# MCU_STM32L011.net
KiCad netlist of a schematic drawn in Altium Designer
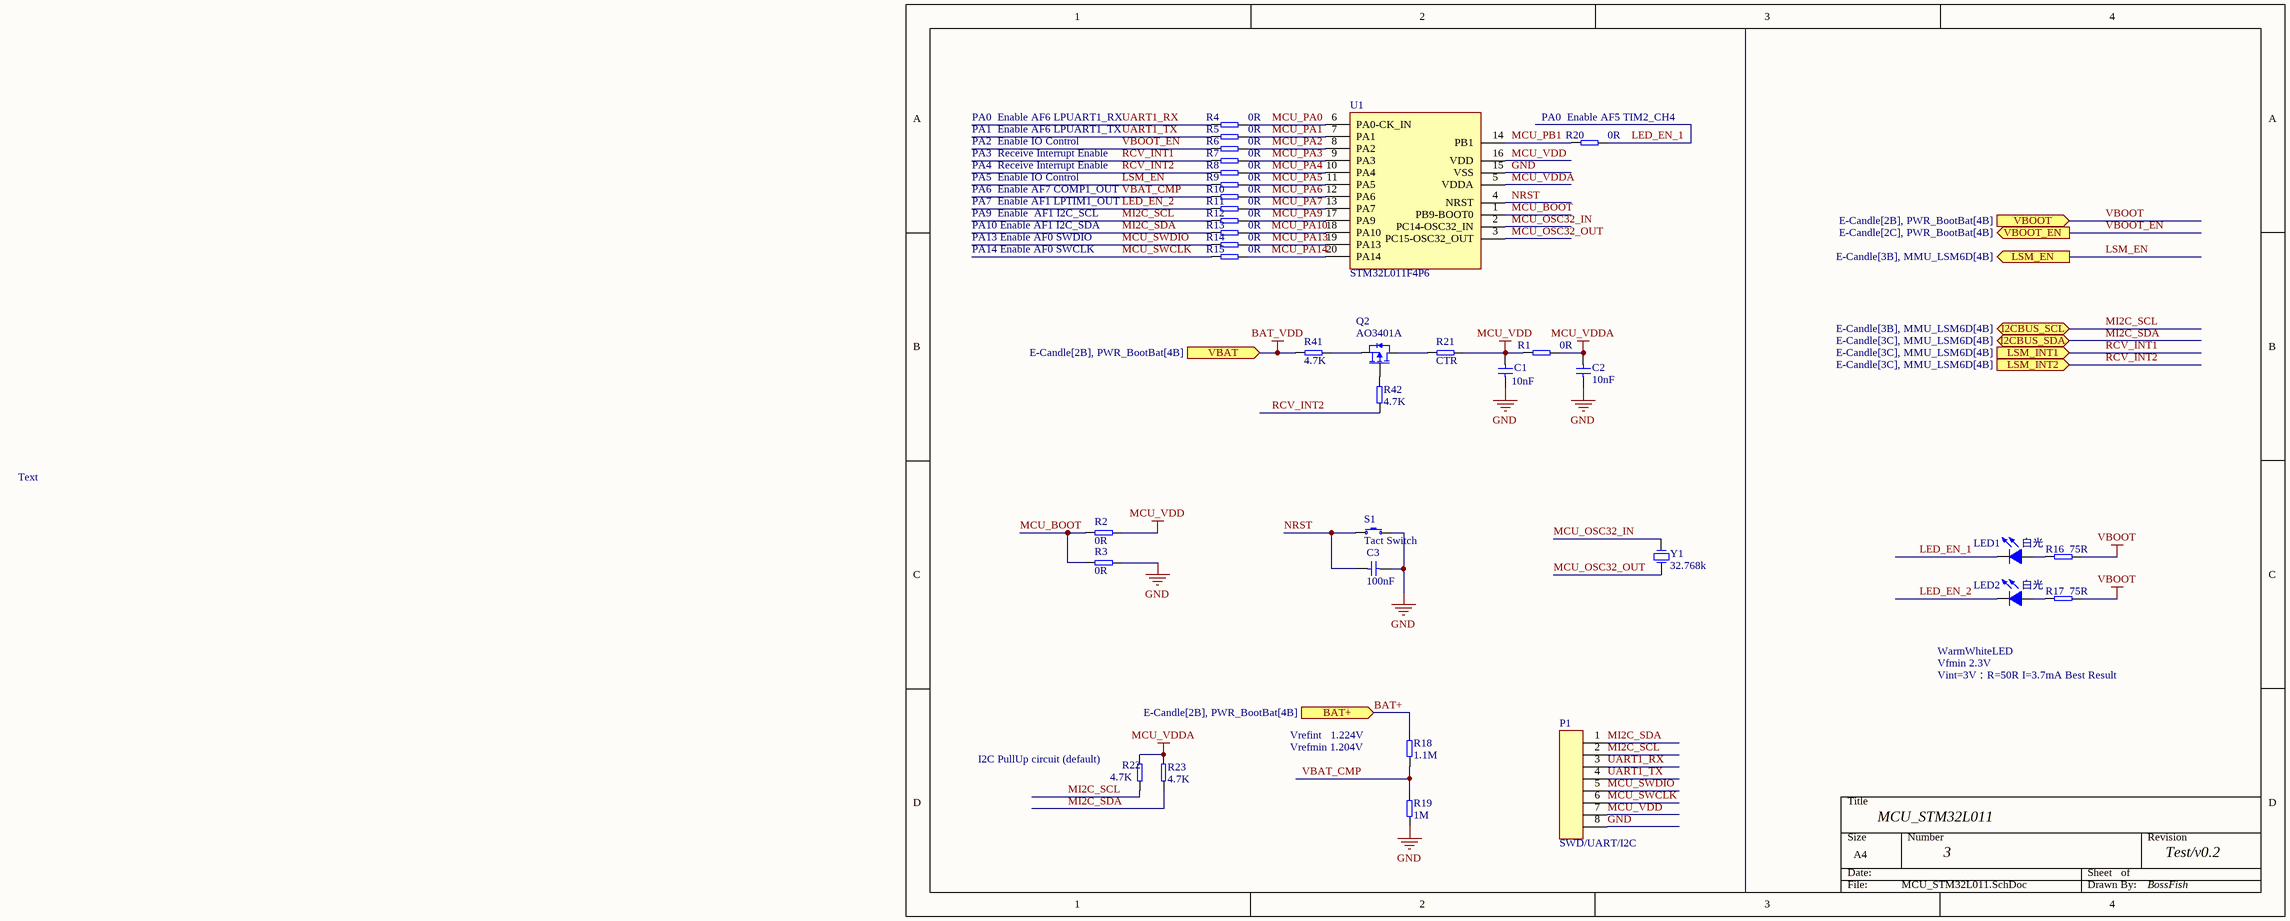
[diagram p0: MCU_STM32L011.SchDoc]

(export (version "E")
  (design (tool "Eeschema 10.0.6"))
  (components
    (comp (ref "C1") (value "10nF") (footprint "0603-C") (libsource (lib "Schlib1") (part "Cap")))
    (comp (ref "C2") (value "10nF") (footprint "0603-C") (libsource (lib "Schlib1") (part "Cap")))
    (comp (ref "C3") (value "100nF") (footprint "0603-C") (libsource (lib "Schlib1") (part "Cap")))
    (comp (ref "LED1") (value "白光") (footprint "0805-LED") (libsource (lib "Schlib1") (part "LED")))
    (comp (ref "LED2") (value "白光") (footprint "0805-LED") (libsource (lib "Schlib1") (part "LED")))
    (comp (ref "P1")
      (value "SWD/UART/I2C")
      (footprint "2.54mm 1x8P")
      (libsource (lib "Schlib1") (part "Header 1x8P"))
    )
    (comp (ref "Q2") (value "AO3401A") (footprint "SOT-23-3") (libsource (lib "Schlib1") (part "MOSFET-P")))
    (comp (ref "R1") (value "0R") (footprint "0603-R") (libsource (lib "Schlib1") (part "Res")))
    (comp (ref "R2") (value "0R") (footprint "0603-R") (libsource (lib "Schlib1") (part "Res")))
    (comp (ref "R3") (value "0R") (footprint "0603-R") (libsource (lib "Schlib1") (part "Res")))
    (comp (ref "R4") (value "0R") (footprint "0603-R") (libsource (lib "Schlib1") (part "Res")))
    (comp (ref "R5") (value "0R") (footprint "0603-R") (libsource (lib "Schlib1") (part "Res")))
    (comp (ref "R6") (value "0R") (footprint "0603-R") (libsource (lib "Schlib1") (part "Res")))
    (comp (ref "R7") (value "0R") (footprint "0603-R") (libsource (lib "Schlib1") (part "Res")))
    (comp (ref "R8") (value "0R") (footprint "0603-R") (libsource (lib "Schlib1") (part "Res")))
    (comp (ref "R9") (value "0R") (footprint "0603-R") (libsource (lib "Schlib1") (part "Res")))
    (comp (ref "R10") (value "0R") (footprint "0603-R") (libsource (lib "Schlib1") (part "Res")))
    (comp (ref "R11") (value "0R") (footprint "0603-R") (libsource (lib "Schlib1") (part "Res")))
    (comp (ref "R12") (value "0R") (footprint "0603-R") (libsource (lib "Schlib1") (part "Res")))
    (comp (ref "R13") (value "0R") (footprint "0603-R") (libsource (lib "Schlib1") (part "Res")))
    (comp (ref "R14") (value "0R") (footprint "0603-R") (libsource (lib "Schlib1") (part "Res")))
    (comp (ref "R15") (value "0R") (footprint "0603-R") (libsource (lib "Schlib1") (part "Res")))
    (comp (ref "R16") (value "75R") (footprint "0603-R") (libsource (lib "Schlib1") (part "Res")))
    (comp (ref "R17") (value "75R") (footprint "0603-R") (libsource (lib "Schlib1") (part "Res")))
    (comp (ref "R18") (value "1.1M") (footprint "0603-R") (libsource (lib "Schlib1") (part "Res")))
    (comp (ref "R19") (value "1M") (footprint "0603-R") (libsource (lib "Schlib1") (part "Res")))
    (comp (ref "R20") (value "0R") (footprint "0603-R") (libsource (lib "Schlib1") (part "Res")))
    (comp (ref "R21") (value "CTR") (footprint "0603-R") (libsource (lib "Schlib1") (part "Res")))
    (comp (ref "R22") (value "4.7K") (footprint "0603-R") (libsource (lib "Schlib1") (part "Res")))
    (comp (ref "R23") (value "4.7K") (footprint "0603-R") (libsource (lib "Schlib1") (part "Res")))
    (comp (ref "R41") (value "4.7K") (footprint "0603-R") (libsource (lib "Schlib1") (part "Res")))
    (comp (ref "R42") (value "4.7K") (footprint "0603-R") (libsource (lib "Schlib1") (part "Res")))
    (comp (ref "S1")
      (value "Tact Switch")
      (footprint "TS-3025")
      (libsource (lib "Schlib1") (part "Tact Switch"))
    )
    (comp (ref "U1")
      (value "STM32L011F4P6")
      (footprint "TSSOP-20")
      (libsource (lib "Schlib1") (part "STM32L011F4P6"))
    )
    (comp (ref "Y1") (value "32.768k") (footprint "SMD3215-2P") (libsource (lib "Schlib1") (part "XTAL")))
  )
  (nets
    (net (code "1") (name "/BAT+") (class "Default")
      (node (ref "R18") (pin "2") (pinfunction "2_2") (pintype "passive"))
    )
    (net (code "2") (name "/LED_EN_1") (class "Default")
      (node (ref "LED1") (pin "1") (pinfunction "1_1") (pintype "passive"))
      (node (ref "R20") (pin "1") (pinfunction "1_1") (pintype "passive"))
    )
    (net (code "3") (name "/LED_EN_2") (class "Default")
      (node (ref "LED2") (pin "1") (pinfunction "1_1") (pintype "passive"))
      (node (ref "R11") (pin "2") (pinfunction "2_2") (pintype "passive"))
    )
    (net (code "4") (name "/LSM_EN") (class "Default")
      (node (ref "R9") (pin "2") (pinfunction "2_2") (pintype "passive"))
    )
    (net (code "5") (name "/MCU_BOOT") (class "Default")
      (node (ref "R2") (pin "2") (pinfunction "2_2") (pintype "passive"))
      (node (ref "R3") (pin "2") (pinfunction "2_2") (pintype "passive"))
      (node (ref "U1") (pin "1") (pinfunction "PB9-BOOT0_1") (pintype "passive"))
    )
    (net (code "6") (name "/MCU_OSC32_IN") (class "Default")
      (node (ref "U1") (pin "2") (pinfunction "PC14-OSC32_IN_2") (pintype "passive"))
      (node (ref "Y1") (pin "2") (pinfunction "2_2") (pintype "passive"))
    )
    (net (code "7") (name "/MCU_OSC32_OUT") (class "Default")
      (node (ref "U1") (pin "3") (pinfunction "PC15-OSC32_OUT_3") (pintype "passive"))
      (node (ref "Y1") (pin "1") (pinfunction "1_1") (pintype "passive"))
    )
    (net (code "8") (name "/MCU_PA0") (class "Default")
      (node (ref "R4") (pin "1") (pinfunction "1_1") (pintype "passive"))
      (node (ref "U1") (pin "6") (pinfunction "PA0-CK_IN_6") (pintype "passive"))
    )
    (net (code "9") (name "/MCU_PA1") (class "Default")
      (node (ref "R5") (pin "1") (pinfunction "1_1") (pintype "passive"))
      (node (ref "U1") (pin "7") (pinfunction "PA1_7") (pintype "passive"))
    )
    (net (code "10") (name "/MCU_PA2") (class "Default")
      (node (ref "R6") (pin "1") (pinfunction "1_1") (pintype "passive"))
      (node (ref "U1") (pin "8") (pinfunction "PA2_8") (pintype "passive"))
    )
    (net (code "11") (name "/MCU_PA3") (class "Default")
      (node (ref "R7") (pin "1") (pinfunction "1_1") (pintype "passive"))
      (node (ref "U1") (pin "9") (pinfunction "PA3_9") (pintype "passive"))
    )
    (net (code "12") (name "/MCU_PA4") (class "Default")
      (node (ref "R8") (pin "1") (pinfunction "1_1") (pintype "passive"))
      (node (ref "U1") (pin "10") (pinfunction "PA4_10") (pintype "passive"))
    )
    (net (code "13") (name "/MCU_PA5") (class "Default")
      (node (ref "R9") (pin "1") (pinfunction "1_1") (pintype "passive"))
      (node (ref "U1") (pin "11") (pinfunction "PA5_11") (pintype "passive"))
    )
    (net (code "14") (name "/MCU_PA6") (class "Default")
      (node (ref "R10") (pin "1") (pinfunction "1_1") (pintype "passive"))
      (node (ref "U1") (pin "12") (pinfunction "PA6_12") (pintype "passive"))
    )
    (net (code "15") (name "/MCU_PA7") (class "Default")
      (node (ref "R11") (pin "1") (pinfunction "1_1") (pintype "passive"))
      (node (ref "U1") (pin "13") (pinfunction "PA7_13") (pintype "passive"))
    )
    (net (code "16") (name "/MCU_PA9") (class "Default")
      (node (ref "R12") (pin "1") (pinfunction "1_1") (pintype "passive"))
      (node (ref "U1") (pin "17") (pinfunction "PA9_17") (pintype "passive"))
    )
    (net (code "17") (name "/MCU_PA10") (class "Default")
      (node (ref "R13") (pin "1") (pinfunction "1_1") (pintype "passive"))
      (node (ref "U1") (pin "18") (pinfunction "PA10_18") (pintype "passive"))
    )
    (net (code "18") (name "/MCU_PA13") (class "Default")
      (node (ref "R14") (pin "1") (pinfunction "1_1") (pintype "passive"))
      (node (ref "U1") (pin "19") (pinfunction "PA13_19") (pintype "passive"))
    )
    (net (code "19") (name "/MCU_PA14") (class "Default")
      (node (ref "R15") (pin "1") (pinfunction "1_1") (pintype "passive"))
      (node (ref "U1") (pin "20") (pinfunction "PA14_20") (pintype "passive"))
    )
    (net (code "20") (name "/MCU_PB1") (class "Default")
      (node (ref "R20") (pin "2") (pinfunction "2_2") (pintype "passive"))
      (node (ref "U1") (pin "14") (pinfunction "PB1_14") (pintype "passive"))
    )
    (net (code "21") (name "/MCU_SWCLK") (class "Default")
      (node (ref "P1") (pin "6") (pinfunction "6_6") (pintype "passive"))
      (node (ref "R15") (pin "2") (pinfunction "2_2") (pintype "passive"))
    )
    (net (code "22") (name "/MCU_SWDIO") (class "Default")
      (node (ref "P1") (pin "5") (pinfunction "5_5") (pintype "passive"))
      (node (ref "R14") (pin "2") (pinfunction "2_2") (pintype "passive"))
    )
    (net (code "23") (name "/MI2C_SCL") (class "Default")
      (node (ref "P1") (pin "2") (pinfunction "2_2") (pintype "passive"))
      (node (ref "R12") (pin "2") (pinfunction "2_2") (pintype "passive"))
      (node (ref "R22") (pin "1") (pinfunction "1_1") (pintype "passive"))
    )
    (net (code "24") (name "/MI2C_SDA") (class "Default")
      (node (ref "P1") (pin "1") (pinfunction "1_1") (pintype "passive"))
      (node (ref "R13") (pin "2") (pinfunction "2_2") (pintype "passive"))
      (node (ref "R23") (pin "1") (pinfunction "1_1") (pintype "passive"))
    )
    (net (code "25") (name "/NRST") (class "Default")
      (node (ref "C3") (pin "1") (pinfunction "1_1") (pintype "passive"))
      (node (ref "S1") (pin "1") (pinfunction "1_1") (pintype "passive"))
      (node (ref "U1") (pin "4") (pinfunction "NRST_4") (pintype "passive"))
    )
    (net (code "26") (name "/RCV_INT1") (class "Default")
      (node (ref "R7") (pin "2") (pinfunction "2_2") (pintype "passive"))
    )
    (net (code "27") (name "/RCV_INT2") (class "Default")
      (node (ref "R42") (pin "2") (pinfunction "2_2") (pintype "passive"))
      (node (ref "R8") (pin "2") (pinfunction "2_2") (pintype "passive"))
    )
    (net (code "28") (name "/UART1_RX") (class "Default")
      (node (ref "P1") (pin "3") (pinfunction "3_3") (pintype "passive"))
      (node (ref "R4") (pin "2") (pinfunction "2_2") (pintype "passive"))
    )
    (net (code "29") (name "/UART1_TX") (class "Default")
      (node (ref "P1") (pin "4") (pinfunction "4_4") (pintype "passive"))
      (node (ref "R5") (pin "2") (pinfunction "2_2") (pintype "passive"))
    )
    (net (code "30") (name "/VBAT_CMP") (class "Default")
      (node (ref "R10") (pin "2") (pinfunction "2_2") (pintype "passive"))
      (node (ref "R18") (pin "1") (pinfunction "1_1") (pintype "passive"))
      (node (ref "R19") (pin "2") (pinfunction "2_2") (pintype "passive"))
    )
    (net (code "31") (name "/VBOOT_EN") (class "Default")
      (node (ref "R6") (pin "2") (pinfunction "2_2") (pintype "passive"))
    )
    (net (code "32") (name "BAT_VDD") (class "Default")
      (node (ref "R41") (pin "2") (pinfunction "2_2") (pintype "passive"))
    )
    (net (code "33") (name "GND") (class "Default")
      (node (ref "C1") (pin "1") (pinfunction "1_1") (pintype "passive"))
      (node (ref "C2") (pin "1") (pinfunction "1_1") (pintype "passive"))
      (node (ref "C3") (pin "2") (pinfunction "2_2") (pintype "passive"))
      (node (ref "P1") (pin "8") (pinfunction "8_8") (pintype "passive"))
      (node (ref "R19") (pin "1") (pinfunction "1_1") (pintype "passive"))
      (node (ref "R3") (pin "1") (pinfunction "1_1") (pintype "passive"))
      (node (ref "S1") (pin "2") (pinfunction "2_2") (pintype "passive"))
      (node (ref "U1") (pin "15") (pinfunction "VSS_15") (pintype "passive"))
    )
    (net (code "34") (name "MCU_VDD") (class "Default")
      (node (ref "C1") (pin "2") (pinfunction "2_2") (pintype "passive"))
      (node (ref "P1") (pin "7") (pinfunction "7_7") (pintype "passive"))
      (node (ref "R1") (pin "2") (pinfunction "2_2") (pintype "passive"))
      (node (ref "R2") (pin "1") (pinfunction "1_1") (pintype "passive"))
      (node (ref "R21") (pin "1") (pinfunction "1_1") (pintype "passive"))
      (node (ref "U1") (pin "16") (pinfunction "VDD_16") (pintype "passive"))
    )
    (net (code "35") (name "MCU_VDDA") (class "Default")
      (node (ref "C2") (pin "2") (pinfunction "2_2") (pintype "passive"))
      (node (ref "R1") (pin "1") (pinfunction "1_1") (pintype "passive"))
      (node (ref "R22") (pin "2") (pinfunction "2_2") (pintype "passive"))
      (node (ref "R23") (pin "2") (pinfunction "2_2") (pintype "passive"))
      (node (ref "U1") (pin "5") (pinfunction "VDDA_5") (pintype "passive"))
    )
    (net (code "36") (name "Net-(LED1-Pad2)") (class "Default")
      (node (ref "LED1") (pin "2") (pinfunction "2_2") (pintype "passive"))
      (node (ref "R16") (pin "1") (pinfunction "1_1") (pintype "passive"))
    )
    (net (code "37") (name "Net-(LED2-Pad2)") (class "Default")
      (node (ref "LED2") (pin "2") (pinfunction "2_2") (pintype "passive"))
      (node (ref "R17") (pin "1") (pinfunction "1_1") (pintype "passive"))
    )
    (net (code "38") (name "Net-(Q2-D)") (class "Default")
      (node (ref "Q2") (pin "1") (pinfunction "D_1") (pintype "passive"))
      (node (ref "R21") (pin "2") (pinfunction "2_2") (pintype "passive"))
    )
    (net (code "39") (name "Net-(Q2-G)") (class "Default")
      (node (ref "Q2") (pin "2") (pinfunction "G_2") (pintype "passive"))
      (node (ref "R42") (pin "1") (pinfunction "1_1") (pintype "passive"))
    )
    (net (code "40") (name "Net-(Q2-S)") (class "Default")
      (node (ref "Q2") (pin "3") (pinfunction "S_3") (pintype "passive"))
      (node (ref "R41") (pin "1") (pinfunction "1_1") (pintype "passive"))
    )
    (net (code "41") (name "VBOOT") (class "Default")
      (node (ref "R16") (pin "2") (pinfunction "2_2") (pintype "passive"))
      (node (ref "R17") (pin "2") (pinfunction "2_2") (pintype "passive"))
    )
  )
)
